# MAX96717_PINOUT.net
KiCad netlist of a schematic drawn in Altium Designer
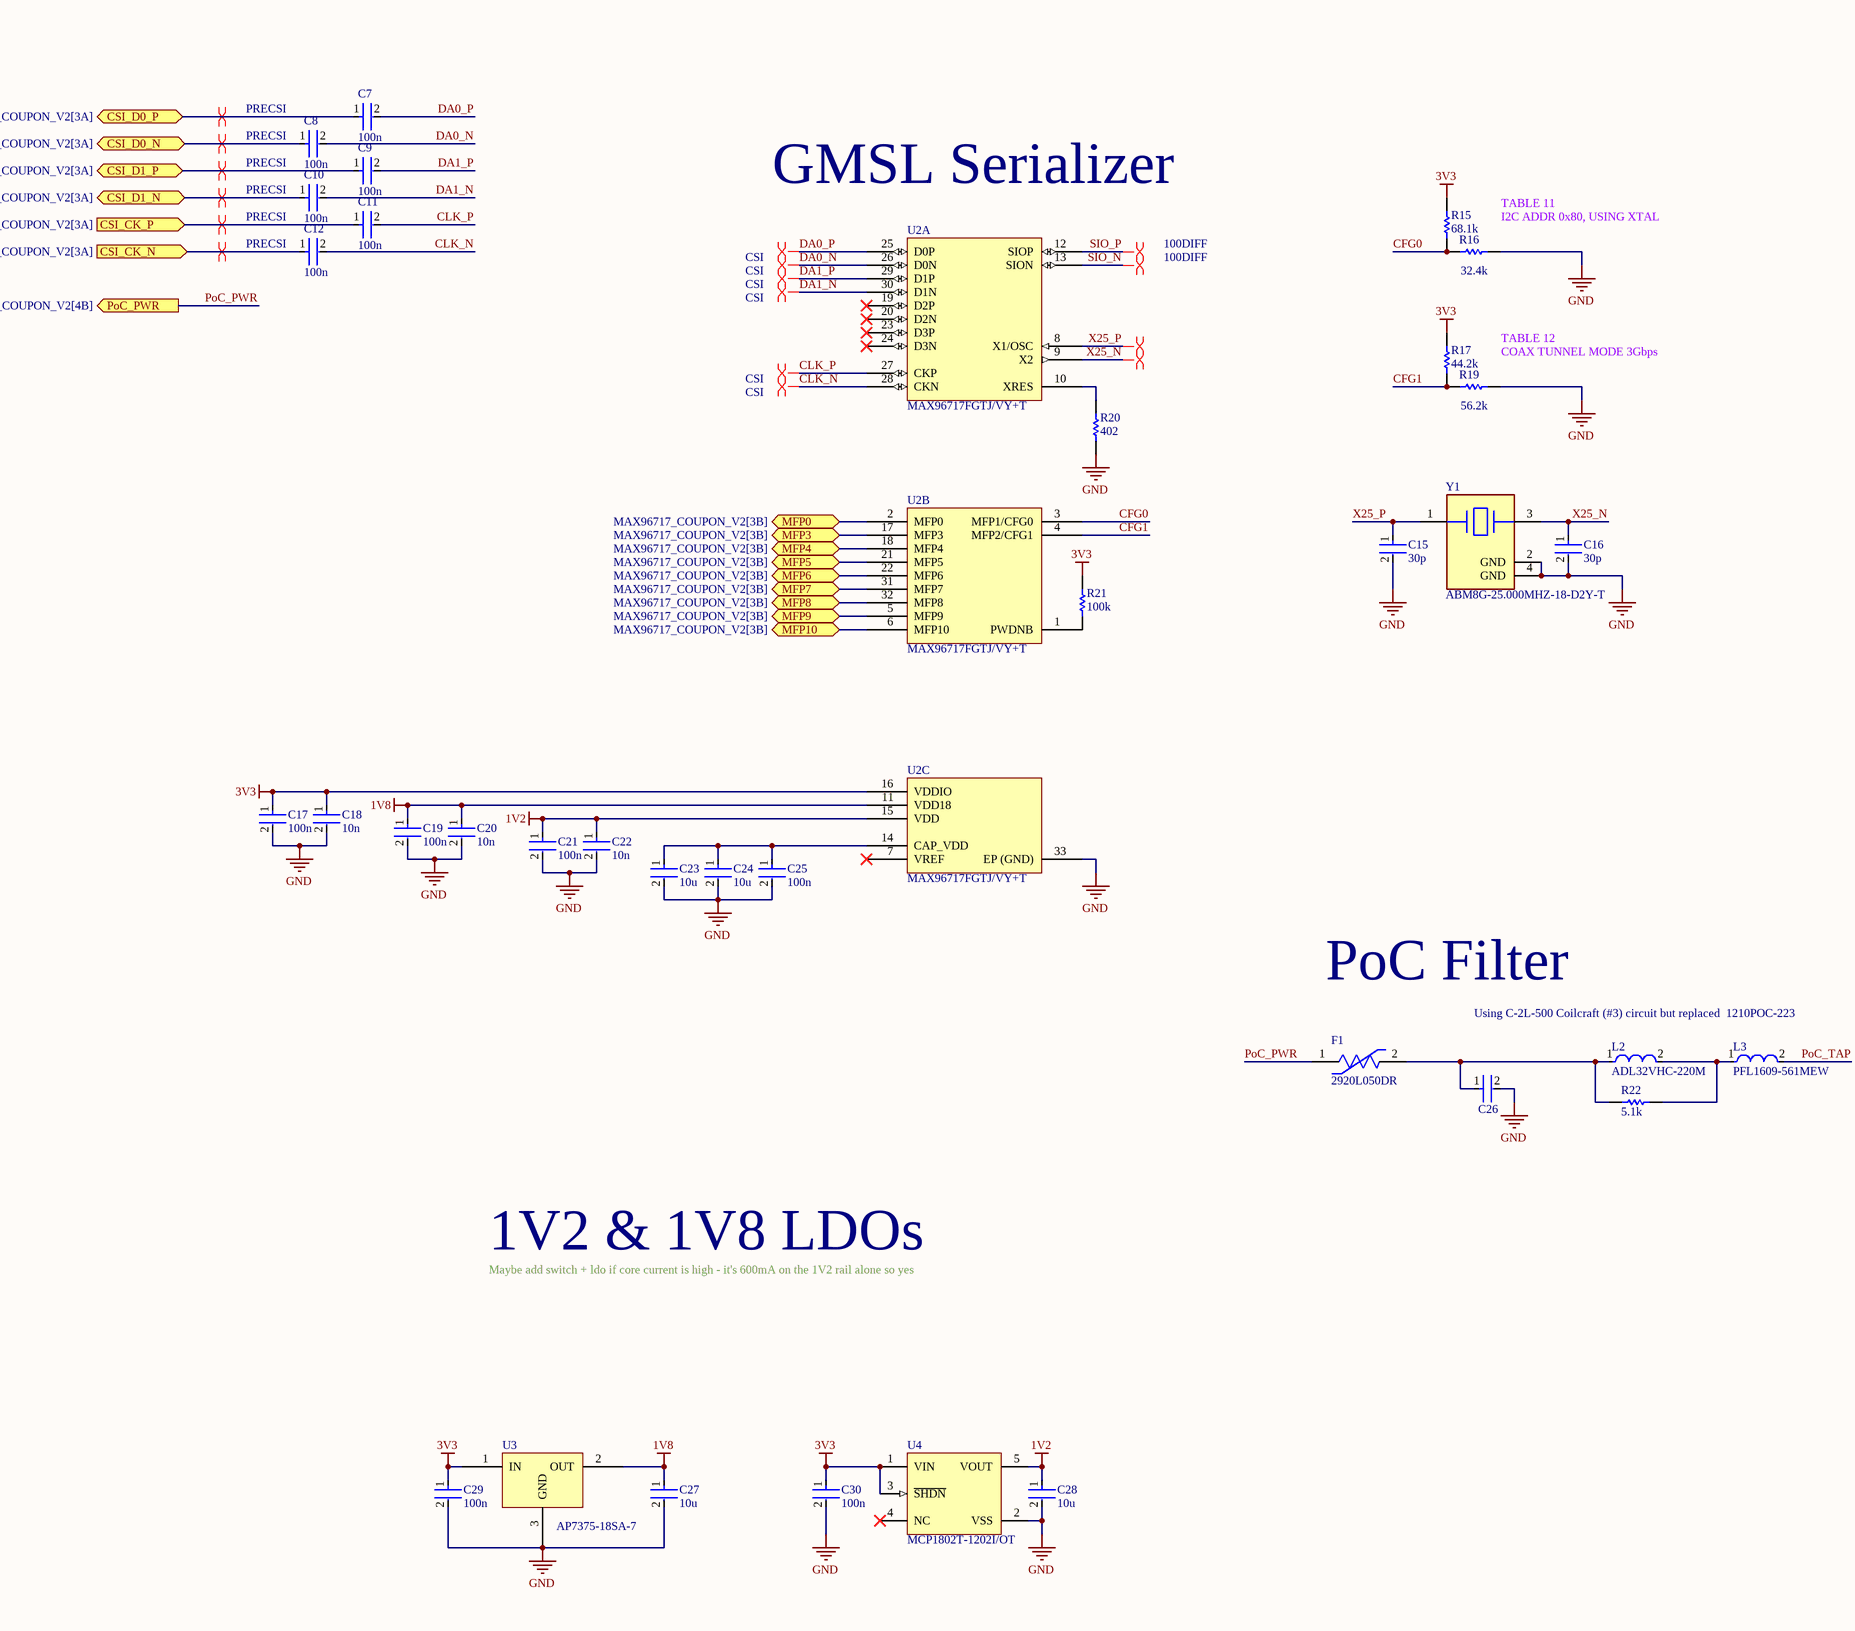
[diagram p0: MAX96717_PINOUT.SchDoc, left]
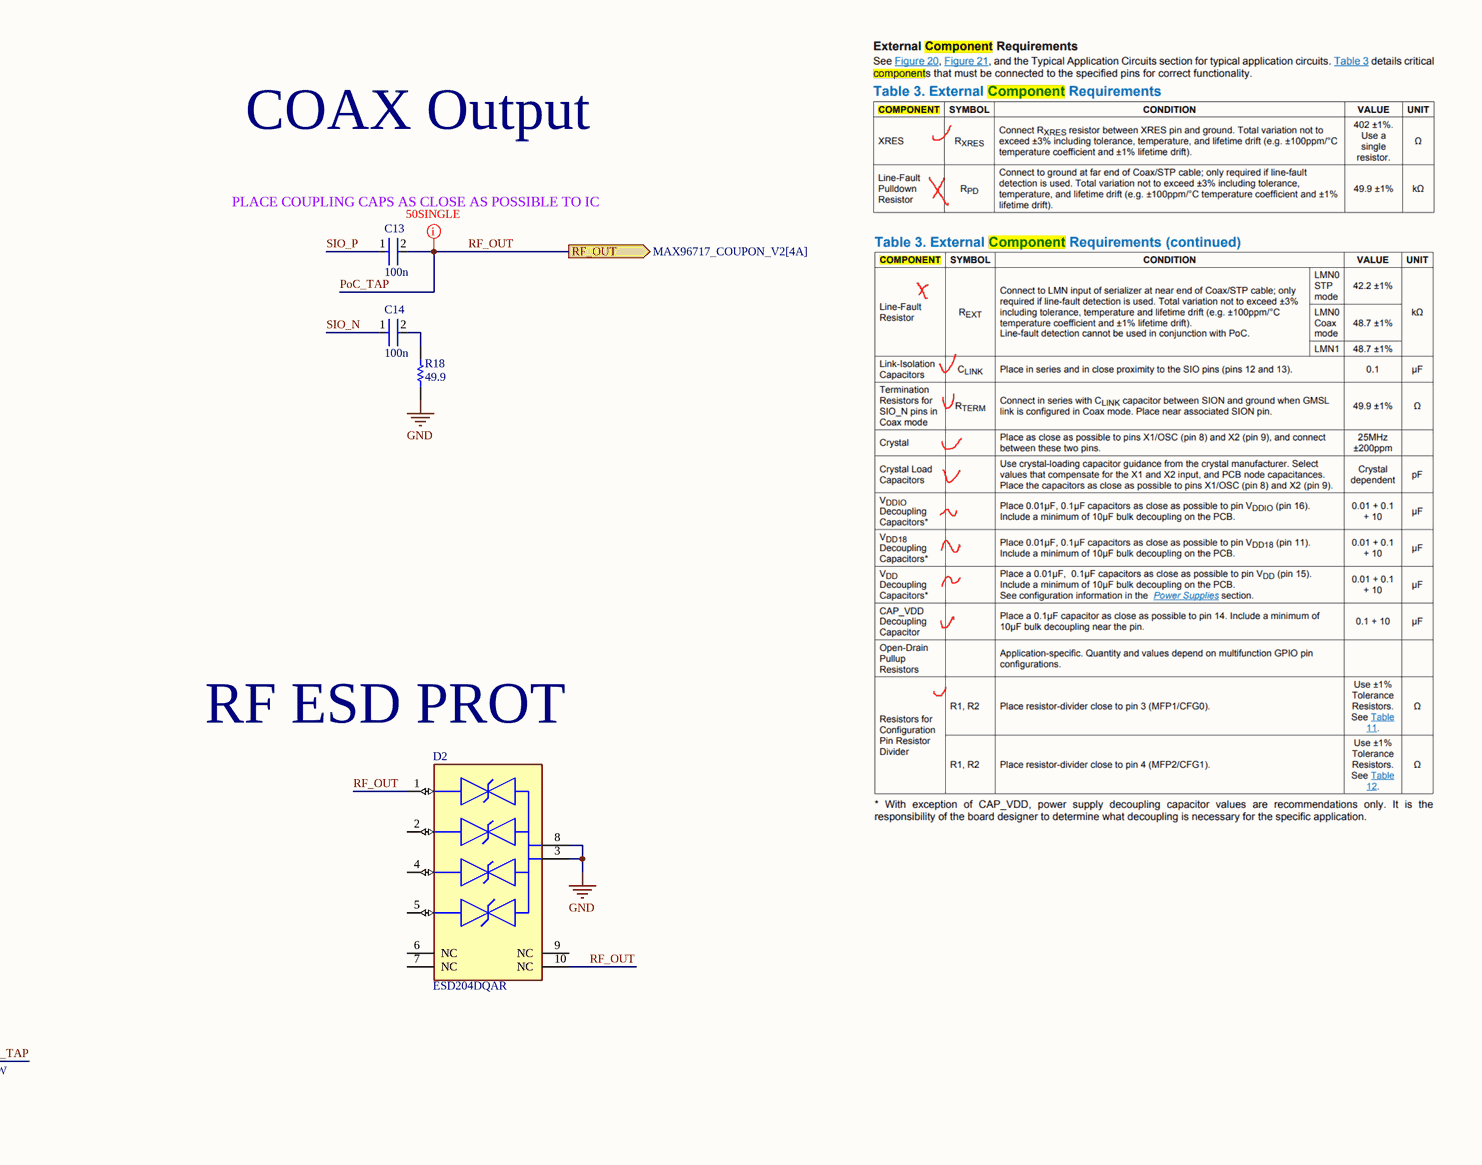
[diagram p1: MAX96717_PINOUT.SchDoc, right]

(export (version "E")
  (design (tool "Eeschema 10.0.6"))
  (components
    (comp (ref "C7")
      (value "100n")
      (footprint "FP-0402-L_1_0_0_05-W_0_5-IPC_A")
      (description "LARGE PADS, 0402 CAP, CHANGE COMMENT TO MATCH REAL P/N")
      (libsource (lib "Space Concordia") (part "b4654b650e69147ec39a6b967a45e02"))
    )
    (comp (ref "C8")
      (value "100n")
      (footprint "FP-0402-L_1_0_0_05-W_0_5-IPC_A")
      (description "LARGE PADS, 0402 CAP, CHANGE COMMENT TO MATCH REAL P/N")
      (libsource (lib "Space Concordia") (part "b4654b650e69147ec39a6b967a45e02"))
    )
    (comp (ref "C9")
      (value "100n")
      (footprint "FP-0402-L_1_0_0_05-W_0_5-IPC_A")
      (description "LARGE PADS, 0402 CAP, CHANGE COMMENT TO MATCH REAL P/N")
      (libsource (lib "Space Concordia") (part "b4654b650e69147ec39a6b967a45e02"))
    )
    (comp (ref "C10")
      (value "100n")
      (footprint "FP-0402-L_1_0_0_05-W_0_5-IPC_A")
      (description "LARGE PADS, 0402 CAP, CHANGE COMMENT TO MATCH REAL P/N")
      (libsource (lib "Space Concordia") (part "b4654b650e69147ec39a6b967a45e02"))
    )
    (comp (ref "C11")
      (value "100n")
      (footprint "FP-0402-L_1_0_0_05-W_0_5-IPC_A")
      (description "LARGE PADS, 0402 CAP, CHANGE COMMENT TO MATCH REAL P/N")
      (libsource (lib "Space Concordia") (part "b4654b650e69147ec39a6b967a45e02"))
    )
    (comp (ref "C12")
      (value "100n")
      (footprint "FP-0402-L_1_0_0_05-W_0_5-IPC_A")
      (description "LARGE PADS, 0402 CAP, CHANGE COMMENT TO MATCH REAL P/N")
      (libsource (lib "Space Concordia") (part "b4654b650e69147ec39a6b967a45e02"))
    )
    (comp (ref "C13")
      (value "100n")
      (footprint "FP-0402-L_1_0_0_05-W_0_5-IPC_A")
      (description "LARGE PADS, 0402 CAP, CHANGE COMMENT TO MATCH REAL P/N")
      (libsource (lib "Space Concordia") (part "b4654b650e69147ec39a6b967a45e02"))
    )
    (comp (ref "C14")
      (value "100n")
      (footprint "FP-0402-L_1_0_0_05-W_0_5-IPC_A")
      (description "LARGE PADS, 0402 CAP, CHANGE COMMENT TO MATCH REAL P/N")
      (libsource (lib "Space Concordia") (part "b4654b650e69147ec39a6b967a45e02"))
    )
    (comp (ref "C15")
      (value "30p")
      (footprint "FP-0402-L_1_0_0_05-W_0_5-IPC_A")
      (description "LARGE PADS, 0402 CAP, CHANGE COMMENT TO MATCH REAL P/N")
      (libsource (lib "Space Concordia") (part "b4654b650e69147ec39a6b967a45e02"))
    )
    (comp (ref "C16")
      (value "30p")
      (footprint "FP-0402-L_1_0_0_05-W_0_5-IPC_A")
      (description "LARGE PADS, 0402 CAP, CHANGE COMMENT TO MATCH REAL P/N")
      (libsource (lib "Space Concordia") (part "b4654b650e69147ec39a6b967a45e02"))
    )
    (comp (ref "C17")
      (value "100n")
      (footprint "FP-0402-L_1_0_0_05-W_0_5-IPC_A")
      (description "LARGE PADS, 0402 CAP, CHANGE COMMENT TO MATCH REAL P/N")
      (libsource (lib "Space Concordia") (part "b4654b650e69147ec39a6b967a45e02"))
    )
    (comp (ref "C18")
      (value "10n")
      (footprint "FP-0402-L_1_0_0_05-W_0_5-IPC_A")
      (description "LARGE PADS, 0402 CAP, CHANGE COMMENT TO MATCH REAL P/N")
      (libsource (lib "Space Concordia") (part "b4654b650e69147ec39a6b967a45e02"))
    )
    (comp (ref "C19")
      (value "100n")
      (footprint "FP-0402-L_1_0_0_05-W_0_5-IPC_A")
      (description "LARGE PADS, 0402 CAP, CHANGE COMMENT TO MATCH REAL P/N")
      (libsource (lib "Space Concordia") (part "b4654b650e69147ec39a6b967a45e02"))
    )
    (comp (ref "C20")
      (value "10n")
      (footprint "FP-0402-L_1_0_0_05-W_0_5-IPC_A")
      (description "LARGE PADS, 0402 CAP, CHANGE COMMENT TO MATCH REAL P/N")
      (libsource (lib "Space Concordia") (part "b4654b650e69147ec39a6b967a45e02"))
    )
    (comp (ref "C21")
      (value "100n")
      (footprint "FP-0402-L_1_0_0_05-W_0_5-IPC_A")
      (description "LARGE PADS, 0402 CAP, CHANGE COMMENT TO MATCH REAL P/N")
      (libsource (lib "Space Concordia") (part "b4654b650e69147ec39a6b967a45e02"))
    )
    (comp (ref "C22")
      (value "10n")
      (footprint "FP-0402-L_1_0_0_05-W_0_5-IPC_A")
      (description "LARGE PADS, 0402 CAP, CHANGE COMMENT TO MATCH REAL P/N")
      (libsource (lib "Space Concordia") (part "b4654b650e69147ec39a6b967a45e02"))
    )
    (comp (ref "C23")
      (value "10u")
      (footprint "FP-0402-L_1_0_0_05-W_0_5-IPC_A")
      (description "LARGE PADS, 0402 CAP, CHANGE COMMENT TO MATCH REAL P/N")
      (libsource (lib "Space Concordia") (part "b4654b650e69147ec39a6b967a45e02"))
    )
    (comp (ref "C24")
      (value "10u")
      (footprint "FP-0402-L_1_0_0_05-W_0_5-IPC_A")
      (description "LARGE PADS, 0402 CAP, CHANGE COMMENT TO MATCH REAL P/N")
      (libsource (lib "Space Concordia") (part "b4654b650e69147ec39a6b967a45e02"))
    )
    (comp (ref "C25")
      (value "100n")
      (footprint "FP-0402-L_1_0_0_05-W_0_5-IPC_A")
      (description "LARGE PADS, 0402 CAP, CHANGE COMMENT TO MATCH REAL P/N")
      (libsource (lib "Space Concordia") (part "b4654b650e69147ec39a6b967a45e02"))
    )
    (comp (ref "C26")
      (value "GRM21BR61E226ME44L")
      (footprint "FP-GRM21B-0_2-e0_2_0_7-IPC_B")
      (description "Chip Multilayer Ceramic Capacitors for General Purpose, 0805, 22uF, X5R, 15%, 20%, 25V")
      (fields (field (name "TOLERANCE") "20%") (field (name "VOLTAGE") "25V"))
      (libsource (lib "Altium Content Vault") (part "b4654b650e69147ec39a6b967a45e02"))
    )
    (comp (ref "C27")
      (value "10u")
      (footprint "FP-0402-L_1_0_0_05-W_0_5-IPC_A")
      (description "LARGE PADS, 0402 CAP, CHANGE COMMENT TO MATCH REAL P/N")
      (libsource (lib "Space Concordia") (part "b4654b650e69147ec39a6b967a45e02"))
    )
    (comp (ref "C28")
      (value "10u")
      (footprint "FP-0402-L_1_0_0_05-W_0_5-IPC_A")
      (description "LARGE PADS, 0402 CAP, CHANGE COMMENT TO MATCH REAL P/N")
      (libsource (lib "Space Concordia") (part "b4654b650e69147ec39a6b967a45e02"))
    )
    (comp (ref "C29")
      (value "100n")
      (footprint "FP-0402-L_1_0_0_05-W_0_5-IPC_A")
      (description "LARGE PADS, 0402 CAP, CHANGE COMMENT TO MATCH REAL P/N")
      (libsource (lib "Space Concordia") (part "b4654b650e69147ec39a6b967a45e02"))
    )
    (comp (ref "C30")
      (value "100n")
      (footprint "FP-0402-L_1_0_0_05-W_0_5-IPC_A")
      (description "LARGE PADS, 0402 CAP, CHANGE COMMENT TO MATCH REAL P/N")
      (libsource (lib "Space Concordia") (part "b4654b650e69147ec39a6b967a45e02"))
    )
    (comp (ref "D2")
      (value "ESD204DQAR")
      (footprint "FP-DQA0010A-MFG")
      (description "4-CHANNEL LOW-CAPACITANCE SURGE")
      (fields
        (field (name "MANUFACTURER") "Texas Instruments")
        (field (name "OCTOPART") "https://octopart.com/esd204dqar-texas+instruments-89917476")
      )
      (libsource (lib "Altium Content Vault") (part "1465e58c1818c7767b55926832f0bf5"))
    )
    (comp (ref "F1")
      (value "2920L050DR")
      (footprint "FP-2920L050DR-MFG")
      (description "PTC RESET FUSE 60V 500MA 2920")
      (libsource (lib "Altium Content Vault") (part "1c6d77a0208143737455a0c7eb396be"))
    )
    (comp (ref "L2")
      (value "ADL32VHC-220M")
      (footprint "FP-1210POC-MFG")
      (description "NOT COILCRAFT - ACTUAL P# --> ADL32VHC-220M\r\n - Power Injection Chokes for PoC")
      (fields
        (field (name "MANUFACTURER") "coilcraft")
        (field (name "OCTOPART") "https://octopart.com/1210poc-223mrc-coilcraft-103207315")
      )
      (libsource (lib "Altium Content Vault") (part "725321dda6339637d4d059423bc1c3c"))
    )
    (comp (ref "L3")
      (value "PFL1609-561MEW")
      (footprint "FP-PFL1609-MFG")
      (description "Fixed Inductors PFL1609 Low Profile 0.56 uH 20 % 1.4 A")
      (fields (field (name "MANUFACTURER") "coilcraft") (field (name "TOLERANCE") "20%"))
      (libsource (lib "Altium Content Vault") (part "725321dda6339637d4d059423bc1c3c"))
    )
    (comp (ref "R15")
      (value "68.1k")
      (footprint "R0603B")
      (description "Resistor")
      (libsource (lib "Space Concordia") (part "Resistor"))
    )
    (comp (ref "R16")
      (value "32.4k")
      (footprint "R0603B")
      (description "Resistor")
      (libsource (lib "Space Concordia") (part "Resistor"))
    )
    (comp (ref "R17")
      (value "44.2k")
      (footprint "R0603B")
      (description "Resistor")
      (libsource (lib "Space Concordia") (part "Resistor"))
    )
    (comp (ref "R18")
      (value "49.9")
      (footprint "R0603B")
      (description "Resistor")
      (libsource (lib "Space Concordia") (part "Resistor"))
    )
    (comp (ref "R19")
      (value "56.2k")
      (footprint "R0603B")
      (description "Resistor")
      (libsource (lib "Space Concordia") (part "Resistor"))
    )
    (comp (ref "R20")
      (value "402")
      (footprint "R0603B")
      (description "Resistor")
      (libsource (lib "Space Concordia") (part "Resistor"))
    )
    (comp (ref "R21")
      (value "100k")
      (footprint "R0603B")
      (description "Resistor")
      (libsource (lib "Space Concordia") (part "Resistor"))
    )
    (comp (ref "R22")
      (value "5.1k")
      (footprint "R0603B")
      (description "Resistor")
      (libsource (lib "Space Concordia") (part "Resistor"))
    )
    (comp (ref "U2")
      (value "MAX96717FGTJ/VY+T")
      (footprint "QFN50P500X500X80_HS-33N")
      (description "3Gbps Serializer TQFN-32 Serializers / Deserializers ROHS")
      (libsource (lib "Space Concordia") (part "MAX96717FGTJ_VY+T"))
    )
    (comp (ref "U3")
      (value "AP7375-18SA-7")
      (footprint "AP7375-18SA-7-Footprint-1")
      (description "Fixed Positive LDO Regulator")
      (libsource (lib "Space Concordia") (part "AP7375-18SA-7"))
    )
    (comp (ref "U4")
      (value "MCP1802T-1202I/OT")
      (footprint "SOT-23-OT5_M")
      (description "300 mA, High PSRR, Low Quiescent Current LDO, 5-Pin SOT-23, Industrial Temperature, Tape and Reel")
      (libsource (lib "Altium Content Vault") (part "PM-LINEREG-MCP1802-IL5"))
    )
    (comp (ref "Y1")
      (value "ABM8G-25.000MHZ-18-D2Y-T")
      (footprint "FP-ABM8G-MFG")
      (description "Crystal 25MHz ±20ppm (Tol) ±30ppm (Stability) 18pF FUND 60Ω 4-Pin SMD T/R")
      (fields (field (name "TOLERANCE") "20ppm"))
      (libsource (lib "Altium Content Vault") (part "48e526d86b7f2615d98721063c72f49"))
    )
  )
  (nets
    (net (code "1") (name "/CFG0") (class "Default")
      (node (ref "R15") (pin "1") (pinfunction "1_1") (pintype "passive"))
      (node (ref "R16") (pin "2") (pinfunction "2_2") (pintype "passive"))
      (node (ref "U2") (pin "3") (pinfunction "MFP1/CFG0_3") (pintype "passive"))
    )
    (net (code "2") (name "/CFG1") (class "Default")
      (node (ref "R17") (pin "1") (pinfunction "1_1") (pintype "passive"))
      (node (ref "R19") (pin "2") (pinfunction "2_2") (pintype "passive"))
      (node (ref "U2") (pin "4") (pinfunction "MFP2/CFG1_4") (pintype "passive"))
    )
    (net (code "3") (name "/CLK_N") (class "Default")
      (node (ref "C12") (pin "2") (pinfunction "2_2") (pintype "passive"))
      (node (ref "U2") (pin "28") (pinfunction "CKN_28") (pintype "bidirectional"))
    )
    (net (code "4") (name "/CLK_P") (class "Default")
      (node (ref "C11") (pin "2") (pinfunction "2_2") (pintype "passive"))
      (node (ref "U2") (pin "27") (pinfunction "CKP_27") (pintype "bidirectional"))
    )
    (net (code "5") (name "/CSI_CK_N") (class "Default")
      (node (ref "C12") (pin "1") (pinfunction "1_1") (pintype "passive"))
    )
    (net (code "6") (name "/CSI_CK_P") (class "Default")
      (node (ref "C11") (pin "1") (pinfunction "1_1") (pintype "passive"))
    )
    (net (code "7") (name "/CSI_D0_N") (class "Default")
      (node (ref "C8") (pin "1") (pinfunction "1_1") (pintype "passive"))
    )
    (net (code "8") (name "/CSI_D0_P") (class "Default")
      (node (ref "C7") (pin "1") (pinfunction "1_1") (pintype "passive"))
    )
    (net (code "9") (name "/CSI_D1_N") (class "Default")
      (node (ref "C10") (pin "1") (pinfunction "1_1") (pintype "passive"))
    )
    (net (code "10") (name "/CSI_D1_P") (class "Default")
      (node (ref "C9") (pin "1") (pinfunction "1_1") (pintype "passive"))
    )
    (net (code "11") (name "/DA0_N") (class "Default")
      (node (ref "C8") (pin "2") (pinfunction "2_2") (pintype "passive"))
      (node (ref "U2") (pin "26") (pinfunction "D0N_26") (pintype "bidirectional"))
    )
    (net (code "12") (name "/DA0_P") (class "Default")
      (node (ref "C7") (pin "2") (pinfunction "2_2") (pintype "passive"))
      (node (ref "U2") (pin "25") (pinfunction "D0P_25") (pintype "bidirectional"))
    )
    (net (code "13") (name "/DA1_N") (class "Default")
      (node (ref "C10") (pin "2") (pinfunction "2_2") (pintype "passive"))
      (node (ref "U2") (pin "30") (pinfunction "D1N_30") (pintype "bidirectional"))
    )
    (net (code "14") (name "/DA1_P") (class "Default")
      (node (ref "C9") (pin "2") (pinfunction "2_2") (pintype "passive"))
      (node (ref "U2") (pin "29") (pinfunction "D1P_29") (pintype "bidirectional"))
    )
    (net (code "15") (name "/MFP0") (class "Default")
      (node (ref "U2") (pin "2") (pinfunction "MFP0_2") (pintype "passive"))
    )
    (net (code "16") (name "/MFP3") (class "Default")
      (node (ref "U2") (pin "17") (pinfunction "MFP3_17") (pintype "passive"))
    )
    (net (code "17") (name "/MFP4") (class "Default")
      (node (ref "U2") (pin "18") (pinfunction "MFP4_18") (pintype "passive"))
    )
    (net (code "18") (name "/MFP5") (class "Default")
      (node (ref "U2") (pin "21") (pinfunction "MFP5_21") (pintype "passive"))
    )
    (net (code "19") (name "/MFP6") (class "Default")
      (node (ref "U2") (pin "22") (pinfunction "MFP6_22") (pintype "passive"))
    )
    (net (code "20") (name "/MFP7") (class "Default")
      (node (ref "U2") (pin "31") (pinfunction "MFP7_31") (pintype "passive"))
    )
    (net (code "21") (name "/MFP8") (class "Default")
      (node (ref "U2") (pin "32") (pinfunction "MFP8_32") (pintype "passive"))
    )
    (net (code "22") (name "/MFP9") (class "Default")
      (node (ref "U2") (pin "5") (pinfunction "MFP9_5") (pintype "passive"))
    )
    (net (code "23") (name "/MFP10") (class "Default")
      (node (ref "U2") (pin "6") (pinfunction "MFP10_6") (pintype "passive"))
    )
    (net (code "24") (name "/PoC_PWR") (class "Default")
      (node (ref "F1") (pin "1") (pinfunction "1_1") (pintype "passive"))
    )
    (net (code "25") (name "/PoC_TAP") (class "Default")
      (node (ref "C13") (pin "2") (pinfunction "2_2") (pintype "passive"))
      (node (ref "D2") (pin "1") (pinfunction "IO1_1") (pintype "bidirectional"))
      (node (ref "D2") (pin "10") (pinfunction "NC_10") (pintype "passive"))
      (node (ref "L3") (pin "2") (pinfunction "2_2") (pintype "passive"))
    )
    (net (code "26") (name "/SIO_N") (class "Default")
      (node (ref "C14") (pin "1") (pinfunction "1_1") (pintype "passive"))
      (node (ref "U2") (pin "13") (pinfunction "SION_13") (pintype "bidirectional"))
    )
    (net (code "27") (name "/SIO_P") (class "Default")
      (node (ref "C13") (pin "1") (pinfunction "1_1") (pintype "passive"))
      (node (ref "U2") (pin "12") (pinfunction "SIOP_12") (pintype "bidirectional"))
    )
    (net (code "28") (name "/X25_N") (class "Default")
      (node (ref "C16") (pin "1") (pinfunction "1_1") (pintype "passive"))
      (node (ref "U2") (pin "9") (pinfunction "X2_9") (pintype "output"))
      (node (ref "Y1") (pin "3") (pinfunction "3_3") (pintype "passive"))
    )
    (net (code "29") (name "/X25_P") (class "Default")
      (node (ref "C15") (pin "1") (pinfunction "1_1") (pintype "passive"))
      (node (ref "U2") (pin "8") (pinfunction "X1/OSC_8") (pintype "input"))
      (node (ref "Y1") (pin "1") (pinfunction "1_1") (pintype "passive"))
    )
    (net (code "30") (name "1V2") (class "Default")
      (node (ref "C21") (pin "1") (pinfunction "1_1") (pintype "passive"))
      (node (ref "C22") (pin "1") (pinfunction "1_1") (pintype "passive"))
      (node (ref "C28") (pin "1") (pinfunction "1_1") (pintype "passive"))
      (node (ref "U2") (pin "15") (pinfunction "VDD_15") (pintype "power_in"))
      (node (ref "U4") (pin "5") (pinfunction "VOUT_5") (pintype "power_in"))
    )
    (net (code "31") (name "1V8") (class "Default")
      (node (ref "C19") (pin "1") (pinfunction "1_1") (pintype "passive"))
      (node (ref "C20") (pin "1") (pinfunction "1_1") (pintype "passive"))
      (node (ref "C27") (pin "1") (pinfunction "1_1") (pintype "passive"))
      (node (ref "U2") (pin "11") (pinfunction "VDD18_11") (pintype "power_in"))
      (node (ref "U3") (pin "2") (pinfunction "OUT_2") (pintype "passive"))
    )
    (net (code "32") (name "3V3") (class "Default")
      (node (ref "C17") (pin "1") (pinfunction "1_1") (pintype "passive"))
      (node (ref "C18") (pin "1") (pinfunction "1_1") (pintype "passive"))
      (node (ref "C29") (pin "1") (pinfunction "1_1") (pintype "passive"))
      (node (ref "C30") (pin "1") (pinfunction "1_1") (pintype "passive"))
      (node (ref "R15") (pin "2") (pinfunction "2_2") (pintype "passive"))
      (node (ref "R17") (pin "2") (pinfunction "2_2") (pintype "passive"))
      (node (ref "R21") (pin "2") (pinfunction "2_2") (pintype "passive"))
      (node (ref "U2") (pin "16") (pinfunction "VDDIO_16") (pintype "power_in"))
      (node (ref "U3") (pin "1") (pinfunction "IN_1") (pintype "passive"))
      (node (ref "U4") (pin "1") (pinfunction "VIN_1") (pintype "power_in"))
      (node (ref "U4") (pin "3") (pinfunction "~{SHDN}_3") (pintype "input"))
    )
    (net (code "33") (name "GND") (class "Default")
      (node (ref "C15") (pin "2") (pinfunction "2_2") (pintype "passive"))
      (node (ref "C16") (pin "2") (pinfunction "2_2") (pintype "passive"))
      (node (ref "C17") (pin "2") (pinfunction "2_2") (pintype "passive"))
      (node (ref "C18") (pin "2") (pinfunction "2_2") (pintype "passive"))
      (node (ref "C19") (pin "2") (pinfunction "2_2") (pintype "passive"))
      (node (ref "C20") (pin "2") (pinfunction "2_2") (pintype "passive"))
      (node (ref "C21") (pin "2") (pinfunction "2_2") (pintype "passive"))
      (node (ref "C22") (pin "2") (pinfunction "2_2") (pintype "passive"))
      (node (ref "C23") (pin "2") (pinfunction "2_2") (pintype "passive"))
      (node (ref "C24") (pin "2") (pinfunction "2_2") (pintype "passive"))
      (node (ref "C25") (pin "2") (pinfunction "2_2") (pintype "passive"))
      (node (ref "C26") (pin "2") (pinfunction "2_2") (pintype "passive"))
      (node (ref "C27") (pin "2") (pinfunction "2_2") (pintype "passive"))
      (node (ref "C28") (pin "2") (pinfunction "2_2") (pintype "passive"))
      (node (ref "C29") (pin "2") (pinfunction "2_2") (pintype "passive"))
      (node (ref "C30") (pin "2") (pinfunction "2_2") (pintype "passive"))
      (node (ref "D2") (pin "3") (pinfunction "GND_3") (pintype "power_in"))
      (node (ref "D2") (pin "8") (pinfunction "GND_8") (pintype "power_in"))
      (node (ref "R16") (pin "1") (pinfunction "1_1") (pintype "passive"))
      (node (ref "R18") (pin "1") (pinfunction "1_1") (pintype "passive"))
      (node (ref "R19") (pin "1") (pinfunction "1_1") (pintype "passive"))
      (node (ref "R20") (pin "1") (pinfunction "1_1") (pintype "passive"))
      (node (ref "U2") (pin "33") (pinfunction "EP_(GND)_33") (pintype "power_in"))
      (node (ref "U3") (pin "3") (pinfunction "GND_3") (pintype "passive"))
      (node (ref "U4") (pin "2") (pinfunction "VSS_2") (pintype "power_in"))
      (node (ref "Y1") (pin "2") (pinfunction "GND_2") (pintype "power_in"))
      (node (ref "Y1") (pin "4") (pinfunction "GND_4") (pintype "power_in"))
    )
    (net (code "34") (name "Net-(C14-Pad2)") (class "Default")
      (node (ref "C14") (pin "2") (pinfunction "2_2") (pintype "passive"))
      (node (ref "R18") (pin "2") (pinfunction "2_2") (pintype "passive"))
    )
    (net (code "35") (name "Net-(C26-Pad1)") (class "Default")
      (node (ref "C26") (pin "1") (pinfunction "1_1") (pintype "passive"))
      (node (ref "F1") (pin "2") (pinfunction "2_2") (pintype "passive"))
      (node (ref "L2") (pin "1") (pinfunction "1_1") (pintype "passive"))
      (node (ref "R22") (pin "2") (pinfunction "2_2") (pintype "passive"))
    )
    (net (code "36") (name "Net-(L2-Pad2)") (class "Default")
      (node (ref "L2") (pin "2") (pinfunction "2_2") (pintype "passive"))
      (node (ref "L3") (pin "1") (pinfunction "1_1") (pintype "passive"))
      (node (ref "R22") (pin "1") (pinfunction "1_1") (pintype "passive"))
    )
    (net (code "37") (name "Net-(U2A-XRES)") (class "Default")
      (node (ref "R20") (pin "2") (pinfunction "2_2") (pintype "passive"))
      (node (ref "U2") (pin "10") (pinfunction "XRES_10") (pintype "passive"))
    )
    (net (code "38") (name "Net-(U2B-PWDNB)") (class "Default")
      (node (ref "R21") (pin "1") (pinfunction "1_1") (pintype "passive"))
      (node (ref "U2") (pin "1") (pinfunction "PWDNB_1") (pintype "passive"))
    )
    (net (code "39") (name "Net-(U2C-CAP_VDD)") (class "Default")
      (node (ref "C23") (pin "1") (pinfunction "1_1") (pintype "passive"))
      (node (ref "C24") (pin "1") (pinfunction "1_1") (pintype "passive"))
      (node (ref "C25") (pin "1") (pinfunction "1_1") (pintype "passive"))
      (node (ref "U2") (pin "14") (pinfunction "CAP_VDD_14") (pintype "power_in"))
    )
    (net (code "40") (name "unconnected-(D2-IO2-Pad2)") (class "Default")
      (node (ref "D2") (pin "2") (pinfunction "IO2_2") (pintype "bidirectional"))
    )
    (net (code "41") (name "unconnected-(D2-IO3-Pad4)") (class "Default")
      (node (ref "D2") (pin "4") (pinfunction "IO3_4") (pintype "bidirectional"))
    )
    (net (code "42") (name "unconnected-(D2-IO4-Pad5)") (class "Default")
      (node (ref "D2") (pin "5") (pinfunction "IO4_5") (pintype "bidirectional"))
    )
    (net (code "43") (name "unconnected-(D2-NC-Pad6)") (class "Default")
      (node (ref "D2") (pin "6") (pinfunction "NC_6") (pintype "passive"))
    )
    (net (code "44") (name "unconnected-(D2-NC-Pad7)") (class "Default")
      (node (ref "D2") (pin "7") (pinfunction "NC_7") (pintype "passive"))
    )
    (net (code "45") (name "unconnected-(D2-NC-Pad9)") (class "Default")
      (node (ref "D2") (pin "9") (pinfunction "NC_9") (pintype "passive"))
    )
    (net (code "46") (name "unconnected-(U2A-D2N-Pad20)") (class "Default")
      (node (ref "U2") (pin "20") (pinfunction "D2N_20") (pintype "bidirectional+no_connect"))
    )
    (net (code "47") (name "unconnected-(U2A-D2P-Pad19)") (class "Default")
      (node (ref "U2") (pin "19") (pinfunction "D2P_19") (pintype "bidirectional+no_connect"))
    )
    (net (code "48") (name "unconnected-(U2A-D3N-Pad24)") (class "Default")
      (node (ref "U2") (pin "24") (pinfunction "D3N_24") (pintype "bidirectional+no_connect"))
    )
    (net (code "49") (name "unconnected-(U2A-D3P-Pad23)") (class "Default")
      (node (ref "U2") (pin "23") (pinfunction "D3P_23") (pintype "bidirectional+no_connect"))
    )
    (net (code "50") (name "unconnected-(U2C-VREF-Pad7)") (class "Default")
      (node (ref "U2") (pin "7") (pinfunction "VREF_7") (pintype "power_in+no_connect"))
    )
    (net (code "51") (name "unconnected-(U4-NC-Pad4)") (class "Default")
      (node (ref "U4") (pin "4") (pinfunction "NC_4") (pintype "passive+no_connect"))
    )
  )
)
